# Serial_I2C_Bridge.net
KiCad netlist of a schematic drawn in EAGLE
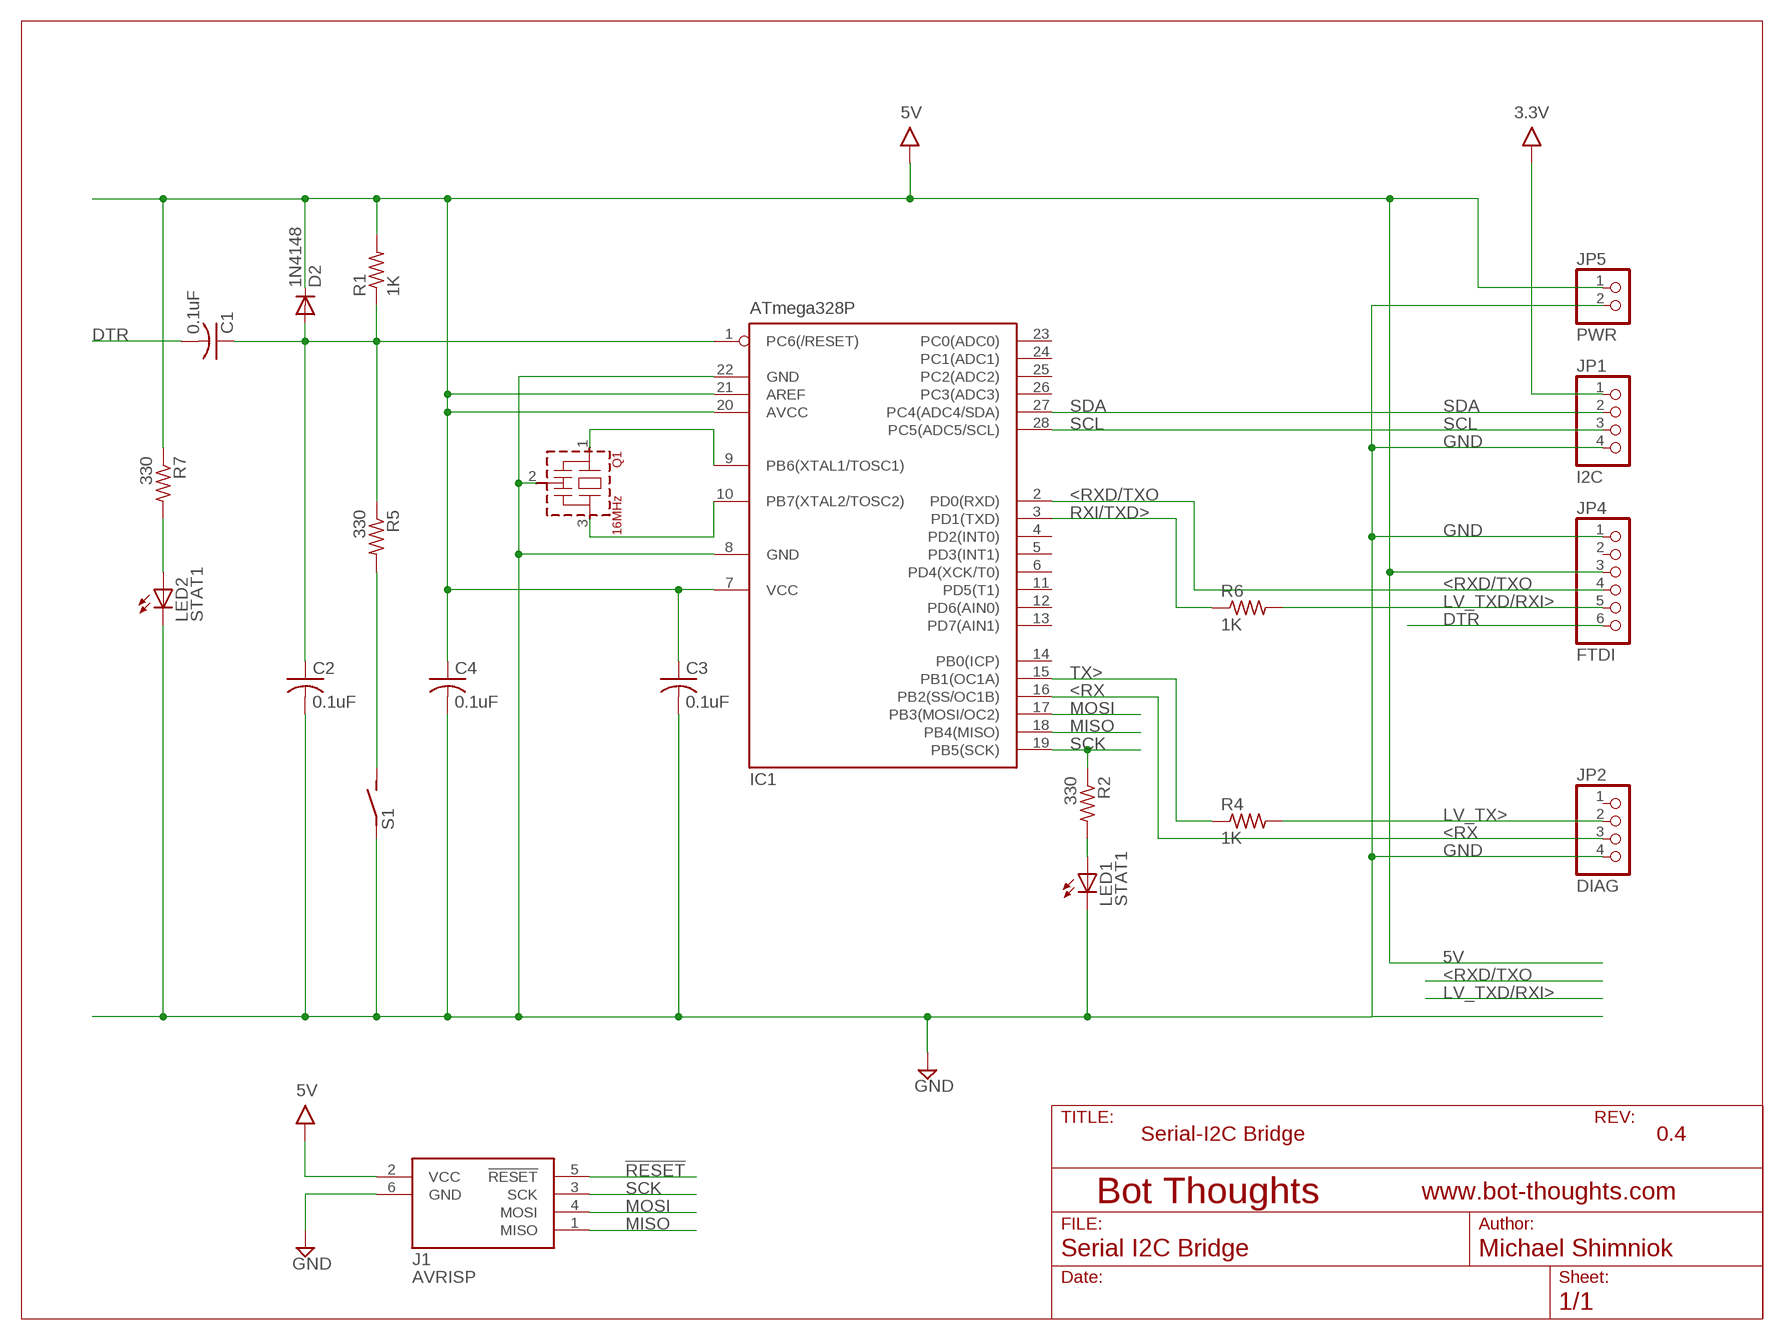
[diagram p0: schematic, sheet 1]

(export (version "E")
  (design (tool "Eeschema 10.0.6"))
  (components
    (comp (ref "C1")
      (value "0.1uF")
      (footprint "eagle-import:C0805")
      (fields (field (name "PARTNO") "CC0603ZRY5V7BB104"))
      (libsource (lib "eagle-import") (part "C-USC0805"))
    )
    (comp (ref "C2")
      (value "0.1uF")
      (footprint "eagle-import:C0805")
      (fields (field (name "PARTNO") "C1608X5R0J105K"))
      (libsource (lib "eagle-import") (part "C-USC0805"))
    )
    (comp (ref "C3")
      (value "0.1uF")
      (footprint "eagle-import:C0805")
      (fields (field (name "PARTNO") "C1608X5R0J105K"))
      (libsource (lib "eagle-import") (part "C-USC0805"))
    )
    (comp (ref "C4")
      (value "0.1uF")
      (footprint "eagle-import:C0805")
      (fields (field (name "PARTNO") "C1608X5R0J105K"))
      (libsource (lib "eagle-import") (part "C-USC0805"))
    )
    (comp (ref "D2")
      (value "1N4148")
      (footprint "eagle-import:DO35-7")
      (libsource (lib "eagle-import") (part "1N4148DO35-7"))
    )
    (comp (ref "IC1")
      (value "ATmega328P")
      (footprint "eagle-import:DIL28-3")
      (fields (field (name "PARTNO") "DEV-10524"))
      (libsource (lib "eagle-import") (part "MEGA8-P"))
    )
    (comp (ref "J1")
      (value "AVRISP")
      (footprint "eagle-import:CON6P2R")
      (libsource (lib "eagle-import") (part "AVRISP6"))
    )
    (comp (ref "JP1")
      (value "I2C")
      (footprint "eagle-import:1X04-S")
      (fields (field (name "PARTNO") "2211S-04G"))
      (libsource (lib "eagle-import") (part "PINHD-1X04_2.54-S"))
    )
    (comp (ref "JP2")
      (value "DIAG")
      (footprint "eagle-import:1X04-S")
      (fields (field (name "PARTNO") "2211S-04G"))
      (libsource (lib "eagle-import") (part "PINHD-1X04_2.54-S"))
    )
    (comp (ref "JP4")
      (value "FTDI")
      (footprint "eagle-import:1X06-S")
      (fields (field (name "PARTNO") "2211S-06G"))
      (libsource (lib "eagle-import") (part "PINHD-1X06_2.54-S"))
    )
    (comp (ref "JP5")
      (value "PWR")
      (footprint "eagle-import:1X02-S")
      (libsource (lib "eagle-import") (part "PINHD-1X02_2.54-S"))
    )
    (comp (ref "LED1")
      (value "STAT1")
      (footprint "eagle-import:LED3MM")
      (libsource (lib "eagle-import") (part "LED3MM"))
    )
    (comp (ref "LED2")
      (value "STAT1")
      (footprint "eagle-import:LED3MM")
      (libsource (lib "eagle-import") (part "LED3MM"))
    )
    (comp (ref "Q1")
      (value "16MHz")
      (footprint "eagle-import:CSTLS_G9")
      (fields (field (name "PARTNO") "AWCR-16.00MD"))
      (libsource (lib "eagle-import") (part "murata-resonators_CSTLS_G"))
    )
    (comp (ref "R1")
      (value "1K")
      (footprint "eagle-import:0204_5")
      (libsource (lib "eagle-import") (part "R-US_0204/5"))
    )
    (comp (ref "R2")
      (value "330")
      (footprint "eagle-import:0204_5")
      (fields (field (name "PARTNO") "CRCW0603330RJNEA"))
      (libsource (lib "eagle-import") (part "R-US_0204/5"))
    )
    (comp (ref "R4")
      (value "1K")
      (footprint "eagle-import:0204_5")
      (fields (field (name "PARTNO") "CRCW0603330RJNEA"))
      (libsource (lib "eagle-import") (part "R-US_0204/5"))
    )
    (comp (ref "R5")
      (value "330")
      (footprint "eagle-import:0204_5")
      (fields (field (name "PARTNO") "CRCW0603330RJNEA"))
      (libsource (lib "eagle-import") (part "R-US_0204/5"))
    )
    (comp (ref "R6")
      (value "1K")
      (footprint "eagle-import:0204_5")
      (fields (field (name "PARTNO") "CRCW0603330RJNEA"))
      (libsource (lib "eagle-import") (part "R-US_0204/5"))
    )
    (comp (ref "R7")
      (value "330")
      (footprint "eagle-import:0204_5")
      (fields (field (name "PARTNO") "CRCW0603330RJNEA"))
      (libsource (lib "eagle-import") (part "R-US_0204/5"))
    )
    (comp (ref "S1")
      (value "RESET\\")
      (footprint "eagle-import:EVQ11X09")
      (fields (field (name "PARTNO") "SALVAGE"))
      (libsource (lib "eagle-import") (part "SPST2EVQ11X09"))
    )
  )
  (nets
    (net (code "1") (name "/<RX") (class "Default")
      (node (ref "IC1") (pin "16") (pinfunction "PB2(SS/OC1B)_16") (pintype "bidirectional"))
      (node (ref "JP2") (pin "3") (pinfunction "3_3") (pintype "passive"))
    )
    (net (code "2") (name "/<RXD{slash}TXO") (class "Default")
      (node (ref "IC1") (pin "2") (pinfunction "PD0(RXD)_2") (pintype "bidirectional"))
      (node (ref "JP4") (pin "4") (pinfunction "4_4") (pintype "passive"))
    )
    (net (code "3") (name "/DTR") (class "Default")
      (node (ref "C1") (pin "2") (pinfunction "2_2") (pintype "passive"))
      (node (ref "JP4") (pin "6") (pinfunction "6_6") (pintype "passive"))
    )
    (net (code "4") (name "/LV_TX>") (class "Default")
      (node (ref "JP2") (pin "2") (pinfunction "2_2") (pintype "passive"))
      (node (ref "R4") (pin "2") (pinfunction "2_2") (pintype "passive"))
    )
    (net (code "5") (name "/LV_TXD{slash}RXI>") (class "Default")
      (node (ref "JP4") (pin "5") (pinfunction "5_5") (pintype "passive"))
      (node (ref "R6") (pin "2") (pinfunction "2_2") (pintype "passive"))
    )
    (net (code "6") (name "/MISO") (class "Default")
      (node (ref "IC1") (pin "18") (pinfunction "PB4(MISO)_18") (pintype "bidirectional"))
      (node (ref "J1") (pin "1") (pinfunction "MISO_1") (pintype "input"))
    )
    (net (code "7") (name "/MOSI") (class "Default")
      (node (ref "IC1") (pin "17") (pinfunction "PB3(MOSI/OC2)_17") (pintype "bidirectional"))
      (node (ref "J1") (pin "4") (pinfunction "MOSI_4") (pintype "output"))
    )
    (net (code "8") (name "/RXI{slash}TXD>") (class "Default")
      (node (ref "IC1") (pin "3") (pinfunction "PD1(TXD)_3") (pintype "bidirectional"))
      (node (ref "R6") (pin "1") (pinfunction "1_1") (pintype "passive"))
    )
    (net (code "9") (name "/SCK") (class "Default")
      (node (ref "IC1") (pin "19") (pinfunction "PB5(SCK)_19") (pintype "bidirectional"))
      (node (ref "J1") (pin "3") (pinfunction "SCK_3") (pintype "output"))
      (node (ref "R2") (pin "1") (pinfunction "1_1") (pintype "passive"))
    )
    (net (code "10") (name "/SCL") (class "Default")
      (node (ref "IC1") (pin "28") (pinfunction "PC5(ADC5/SCL)_28") (pintype "bidirectional"))
      (node (ref "JP1") (pin "3") (pinfunction "3_3") (pintype "passive"))
    )
    (net (code "11") (name "/SDA") (class "Default")
      (node (ref "IC1") (pin "27") (pinfunction "PC4(ADC4/SDA)_27") (pintype "bidirectional"))
      (node (ref "JP1") (pin "2") (pinfunction "2_2") (pintype "passive"))
    )
    (net (code "12") (name "/TX>") (class "Default")
      (node (ref "IC1") (pin "15") (pinfunction "PB1(OC1A)_15") (pintype "bidirectional"))
      (node (ref "R4") (pin "1") (pinfunction "1_1") (pintype "passive"))
    )
    (net (code "13") (name "/~{RESET}") (class "Default")
      (node (ref "C1") (pin "1") (pinfunction "1_1") (pintype "passive"))
      (node (ref "C2") (pin "1") (pinfunction "1_1") (pintype "passive"))
      (node (ref "D2") (pin "A") (pinfunction "A_A") (pintype "passive"))
      (node (ref "IC1") (pin "1") (pinfunction "PC6(/RESET)_1") (pintype "bidirectional"))
      (node (ref "J1") (pin "5") (pinfunction "~{RESET}_5") (pintype "output"))
      (node (ref "R1") (pin "1") (pinfunction "1_1") (pintype "passive"))
      (node (ref "R5") (pin "1") (pinfunction "1_1") (pintype "passive"))
    )
    (net (code "14") (name "3.3V") (class "Default")
      (node (ref "JP1") (pin "1") (pinfunction "1_1") (pintype "passive"))
    )
    (net (code "15") (name "5V") (class "Default")
      (node (ref "C3") (pin "1") (pinfunction "1_1") (pintype "passive"))
      (node (ref "C4") (pin "1") (pinfunction "1_1") (pintype "passive"))
      (node (ref "D2") (pin "C") (pinfunction "C_C") (pintype "passive"))
      (node (ref "IC1") (pin "20") (pinfunction "AVCC_20") (pintype "power_in"))
      (node (ref "IC1") (pin "21") (pinfunction "AREF_21") (pintype "passive"))
      (node (ref "IC1") (pin "7") (pinfunction "VCC_7") (pintype "power_in"))
      (node (ref "J1") (pin "2") (pinfunction "VCC_2") (pintype "power_in"))
      (node (ref "JP4") (pin "3") (pinfunction "3_3") (pintype "passive"))
      (node (ref "JP5") (pin "1") (pinfunction "1_1") (pintype "passive"))
      (node (ref "R1") (pin "2") (pinfunction "2_2") (pintype "passive"))
      (node (ref "R7") (pin "1") (pinfunction "1_1") (pintype "passive"))
    )
    (net (code "16") (name "GND") (class "Default")
      (node (ref "C2") (pin "2") (pinfunction "2_2") (pintype "passive"))
      (node (ref "C3") (pin "2") (pinfunction "2_2") (pintype "passive"))
      (node (ref "C4") (pin "2") (pinfunction "2_2") (pintype "passive"))
      (node (ref "IC1") (pin "22") (pinfunction "GND_22") (pintype "power_in"))
      (node (ref "IC1") (pin "8") (pinfunction "GND_8") (pintype "power_in"))
      (node (ref "J1") (pin "6") (pinfunction "GND_6") (pintype "power_in"))
      (node (ref "JP1") (pin "4") (pinfunction "4_4") (pintype "passive"))
      (node (ref "JP2") (pin "4") (pinfunction "4_4") (pintype "passive"))
      (node (ref "JP4") (pin "1") (pinfunction "1_1") (pintype "passive"))
      (node (ref "JP5") (pin "2") (pinfunction "2_2") (pintype "passive"))
      (node (ref "LED1") (pin "K") (pinfunction "C_K") (pintype "passive"))
      (node (ref "LED2") (pin "K") (pinfunction "C_K") (pintype "passive"))
      (node (ref "Q1") (pin "2") (pinfunction "VSS_2") (pintype "power_in"))
      (node (ref "S1") (pin "1") (pinfunction "1_1") (pintype "passive"))
    )
    (net (code "17") (name "Net-(IC1-PB6(XTAL1{slash}TOSC1))") (class "Default")
      (node (ref "IC1") (pin "9") (pinfunction "PB6(XTAL1/TOSC1)_9") (pintype "bidirectional"))
      (node (ref "Q1") (pin "1") (pinfunction "1_1") (pintype "output"))
    )
    (net (code "18") (name "Net-(IC1-PB7(XTAL2{slash}TOSC2))") (class "Default")
      (node (ref "IC1") (pin "10") (pinfunction "PB7(XTAL2/TOSC2)_10") (pintype "bidirectional"))
      (node (ref "Q1") (pin "3") (pinfunction "3_3") (pintype "input"))
    )
    (net (code "19") (name "Net-(LED1-PadA)") (class "Default")
      (node (ref "LED1") (pin "A") (pinfunction "A_A") (pintype "passive"))
      (node (ref "R2") (pin "2") (pinfunction "2_2") (pintype "passive"))
    )
    (net (code "20") (name "Net-(LED2-PadA)") (class "Default")
      (node (ref "LED2") (pin "A") (pinfunction "A_A") (pintype "passive"))
      (node (ref "R7") (pin "2") (pinfunction "2_2") (pintype "passive"))
    )
    (net (code "21") (name "Net-(R5-Pad2)") (class "Default")
      (node (ref "R5") (pin "2") (pinfunction "2_2") (pintype "passive"))
      (node (ref "S1") (pin "2") (pinfunction "2_2") (pintype "passive"))
    )
    (net (code "22") (name "unconnected-(IC1-PB0(ICP)-Pad14)") (class "Default")
      (node (ref "IC1") (pin "14") (pinfunction "PB0(ICP)_14") (pintype "bidirectional"))
    )
    (net (code "23") (name "unconnected-(IC1-PC0(ADC0)-Pad23)") (class "Default")
      (node (ref "IC1") (pin "23") (pinfunction "PC0(ADC0)_23") (pintype "bidirectional"))
    )
    (net (code "24") (name "unconnected-(IC1-PC1(ADC1)-Pad24)") (class "Default")
      (node (ref "IC1") (pin "24") (pinfunction "PC1(ADC1)_24") (pintype "bidirectional"))
    )
    (net (code "25") (name "unconnected-(IC1-PC2(ADC2)-Pad25)") (class "Default")
      (node (ref "IC1") (pin "25") (pinfunction "PC2(ADC2)_25") (pintype "bidirectional"))
    )
    (net (code "26") (name "unconnected-(IC1-PC3(ADC3)-Pad26)") (class "Default")
      (node (ref "IC1") (pin "26") (pinfunction "PC3(ADC3)_26") (pintype "bidirectional"))
    )
    (net (code "27") (name "unconnected-(IC1-PD2(INT0)-Pad4)") (class "Default")
      (node (ref "IC1") (pin "4") (pinfunction "PD2(INT0)_4") (pintype "bidirectional"))
    )
    (net (code "28") (name "unconnected-(IC1-PD3(INT1)-Pad5)") (class "Default")
      (node (ref "IC1") (pin "5") (pinfunction "PD3(INT1)_5") (pintype "bidirectional"))
    )
    (net (code "29") (name "unconnected-(IC1-PD4(XCK{slash}T0)-Pad6)") (class "Default")
      (node (ref "IC1") (pin "6") (pinfunction "PD4(XCK/T0)_6") (pintype "bidirectional"))
    )
    (net (code "30") (name "unconnected-(IC1-PD5(T1)-Pad11)") (class "Default")
      (node (ref "IC1") (pin "11") (pinfunction "PD5(T1)_11") (pintype "bidirectional"))
    )
    (net (code "31") (name "unconnected-(IC1-PD6(AIN0)-Pad12)") (class "Default")
      (node (ref "IC1") (pin "12") (pinfunction "PD6(AIN0)_12") (pintype "bidirectional"))
    )
    (net (code "32") (name "unconnected-(IC1-PD7(AIN1)-Pad13)") (class "Default")
      (node (ref "IC1") (pin "13") (pinfunction "PD7(AIN1)_13") (pintype "bidirectional"))
    )
    (net (code "33") (name "unconnected-(JP2-Pad1)") (class "Default")
      (node (ref "JP2") (pin "1") (pinfunction "1_1") (pintype "passive"))
    )
    (net (code "34") (name "unconnected-(JP4-Pad2)") (class "Default")
      (node (ref "JP4") (pin "2") (pinfunction "2_2") (pintype "passive"))
    )
  )
)
